# Sheet1.net
KiCad netlist of a schematic drawn in Altium Designer
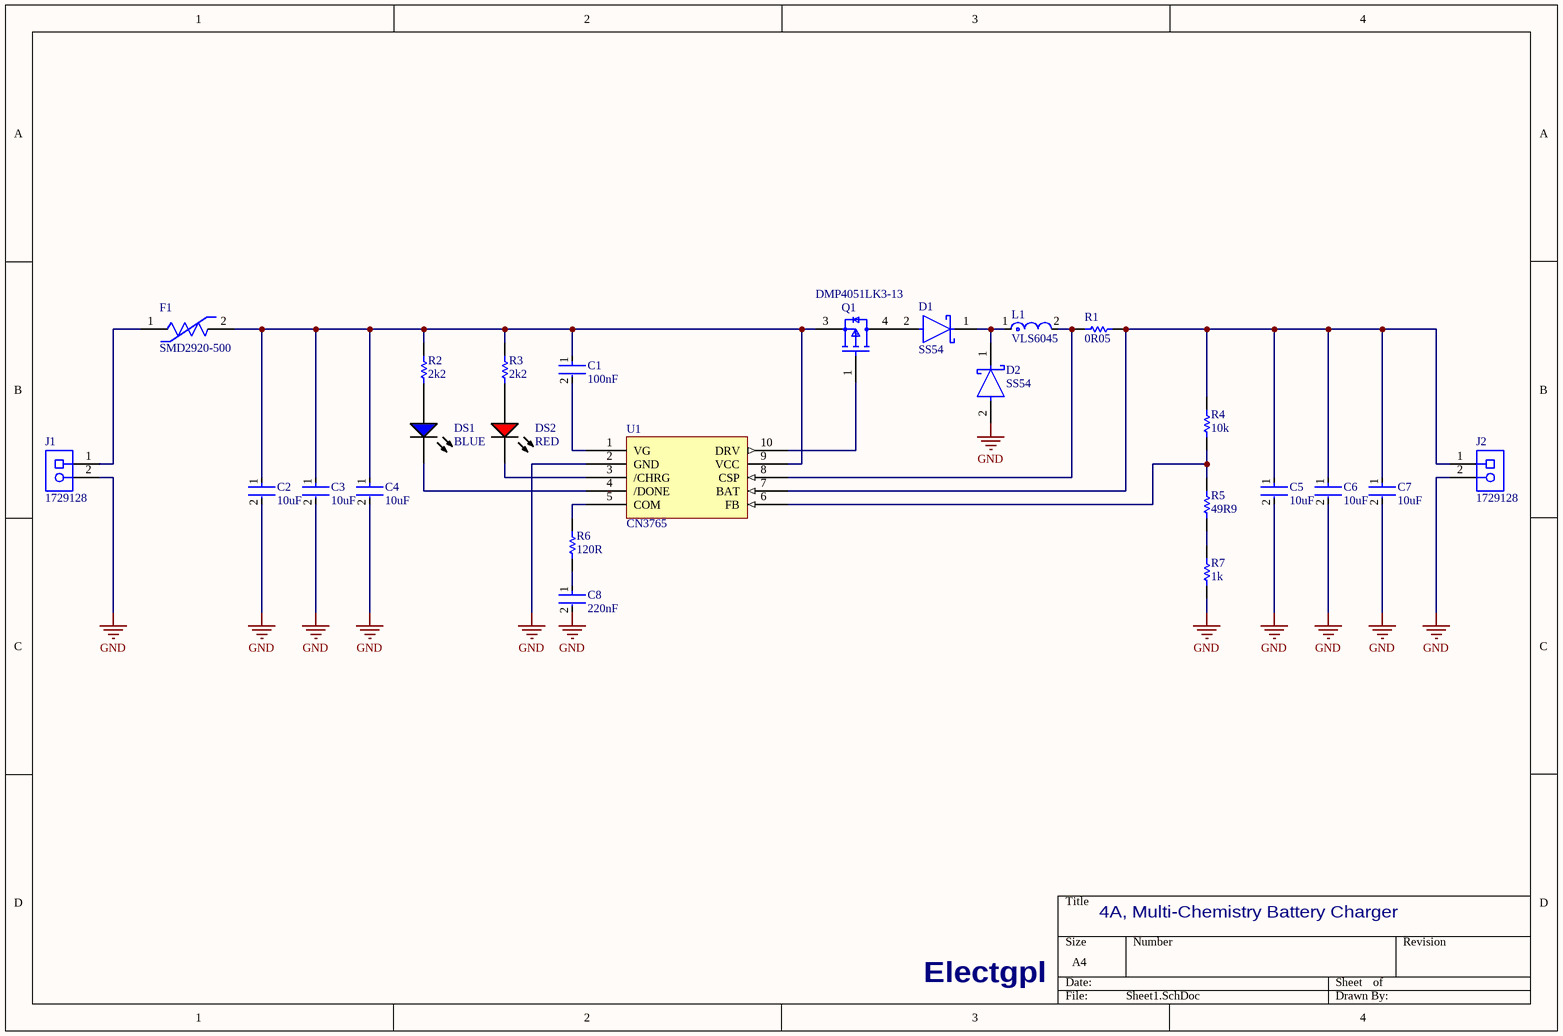
[diagram p0: Sheet1.SchDoc]

(export (version "E")
  (design (tool "Eeschema 10.0.6"))
  (components
    (comp (ref "C1")
      (value "100nF")
      (footprint "FP-C0603C-CF-MFG")
      (description "CAP CER 0.22UF 25V 10% X7R 0603")
      (fields
        (field (name "MANUFACTURER") "KEMET")
        (field (name "MANUFACTURER PART NUMBER") "C0603C224K3RACTU")
      )
      (libsource (lib "Altium Content Vault") (part "b4654b650e69147ec39a6b967a45e02"))
    )
    (comp (ref "C2")
      (value "10uF")
      (footprint "FP-GRM21B-0_1-IPC_C")
      (description "Chip Multilayer Ceramic Capacitors for General Purpose, 0805, 10uF, X5R, 15%, 10%, 16V")
      (fields (field (name "TOLERANCE") "10%") (field (name "VOLTAGE") "16V"))
      (libsource (lib "Altium Content Vault") (part "b4654b650e69147ec39a6b967a45e02"))
    )
    (comp (ref "C3")
      (value "10uF")
      (footprint "FP-GRM21B-0_1-IPC_C")
      (description "Chip Multilayer Ceramic Capacitors for General Purpose, 0805, 10uF, X5R, 15%, 10%, 16V")
      (fields (field (name "TOLERANCE") "10%") (field (name "VOLTAGE") "16V"))
      (libsource (lib "Altium Content Vault") (part "b4654b650e69147ec39a6b967a45e02"))
    )
    (comp (ref "C4")
      (value "10uF")
      (footprint "FP-GRM21B-0_1-IPC_C")
      (description "Chip Multilayer Ceramic Capacitors for General Purpose, 0805, 10uF, X5R, 15%, 10%, 16V")
      (fields (field (name "TOLERANCE") "10%") (field (name "VOLTAGE") "16V"))
      (libsource (lib "Altium Content Vault") (part "b4654b650e69147ec39a6b967a45e02"))
    )
    (comp (ref "C5")
      (value "10uF")
      (footprint "FP-GRM21B-0_1-IPC_C")
      (description "Chip Multilayer Ceramic Capacitors for General Purpose, 0805, 10uF, X5R, 15%, 10%, 16V")
      (fields (field (name "TOLERANCE") "10%") (field (name "VOLTAGE") "16V"))
      (libsource (lib "Altium Content Vault") (part "b4654b650e69147ec39a6b967a45e02"))
    )
    (comp (ref "C6")
      (value "10uF")
      (footprint "FP-GRM21B-0_1-IPC_C")
      (description "Chip Multilayer Ceramic Capacitors for General Purpose, 0805, 10uF, X5R, 15%, 10%, 16V")
      (fields (field (name "TOLERANCE") "10%") (field (name "VOLTAGE") "16V"))
      (libsource (lib "Altium Content Vault") (part "b4654b650e69147ec39a6b967a45e02"))
    )
    (comp (ref "C7")
      (value "10uF")
      (footprint "FP-GRM21B-0_1-IPC_C")
      (description "Chip Multilayer Ceramic Capacitors for General Purpose, 0805, 10uF, X5R, 15%, 10%, 16V")
      (fields (field (name "TOLERANCE") "10%") (field (name "VOLTAGE") "16V"))
      (libsource (lib "Altium Content Vault") (part "b4654b650e69147ec39a6b967a45e02"))
    )
    (comp (ref "C8")
      (value "220nF")
      (footprint "FP-C0603C-CF-MFG")
      (description "CAP CER 0.22UF 25V 10% X7R 0603")
      (fields
        (field (name "MANUFACTURER") "KEMET")
        (field (name "MANUFACTURER PART NUMBER") "C0603C224K3RACTU")
      )
      (libsource (lib "Altium Content Vault") (part "b4654b650e69147ec39a6b967a45e02"))
    )
    (comp (ref "D1")
      (value "SS54")
      (footprint "FP-SMB-MFG")
      (description "DIODE SCHOTTKY 150V 3A SMB")
      (fields
        (field (name "MANUFACTURER PART NUMBER") "STPS3150U")
        (field (name "OCTOPART") "https://octopart.com/stps3150u-stmicroelectronics-39552976")
      )
      (libsource (lib "Altium Content Vault") (part "fefb30dabb5d097ae2f038500735429"))
    )
    (comp (ref "D2")
      (value "SS54")
      (footprint "FP-SMB-MFG")
      (description "DIODE SCHOTTKY 150V 3A SMB")
      (fields
        (field (name "MANUFACTURER PART NUMBER") "STPS3150U")
        (field (name "OCTOPART") "https://octopart.com/stps3150u-stmicroelectronics-39552976")
      )
      (libsource (lib "Altium Content Vault") (part "fefb30dabb5d097ae2f038500735429"))
    )
    (comp (ref "DS1")
      (value "BLUE")
      (footprint "VISH-TLMX1100-2_V")
      (description "Blue LED, 10 mA, 3.9 V, -40 to 100 degC, 2-Pin SMD (0603), RoHS, Tape and Reel")
      (fields (field (name "TOLERANCE") "10%"))
      (libsource (lib "Altium Content Vault") (part "LED-BLUE-AK-2"))
    )
    (comp (ref "DS2")
      (value "RED")
      (footprint "VISH-TLMS1000_V")
      (description "Low Current LED, 40 mW, 1.8 V, -40 to 100 degC, 2-Pin SMD (0603), RoHS, Tape and Reel")
      (fields (field (name "MANUFACTURER") "Vishay"))
      (libsource (lib "Altium Content Vault") (part "LED-RED-AK-2"))
    )
    (comp (ref "F1")
      (value "SMD2920-500")
      (footprint "FP-2920L-MFG")
      (description "PTC RESET FUSE 60V 1.1A 2920")
      (fields
        (field (name "MANUFACTURER PART NUMBER") "2920L110/60MR")
        (field (name "MANUFACTURER") "Littelfuse")
      )
      (libsource (lib "Altium Content Vault") (part "fc31388045fc42ab786d6d00b506e9f"))
    )
    (comp (ref "J1")
      (value "1729128")
      (footprint "PHOE-1729128-2_V")
      (description "PCB Terminal Block, 13.5 A, 400 V, 2-Pin THD, RoHS, Bulk")
      (fields (field (name "MANUFACTURER") "Phoenix Contact"))
      (libsource (lib "Altium Content Vault") (part "CN-2P-F-R2"))
    )
    (comp (ref "J2")
      (value "1729128")
      (footprint "PHOE-1729128-2_V")
      (description "PCB Terminal Block, 13.5 A, 400 V, 2-Pin THD, RoHS, Bulk")
      (fields (field (name "MANUFACTURER") "Phoenix Contact"))
      (libsource (lib "") (part "CN-2P-F-R2_1"))
    )
    (comp (ref "L1")
      (value "VLS6045")
      (footprint "FP-VLS6045EX-100M-MFG")
      (description "FIXED IND 10UH 3.4A 61 MOHM SMD")
      (fields (field (name "TOLERANCE") "20%"))
      (libsource (lib "Altium Content Vault") (part "4cc4b267dca4c8e51f7102f422741d8"))
    )
    (comp (ref "Q1")
      (value "DMP4051LK3-13")
      (footprint "FP-TO252-MFG")
      (description "MOSFET P-CH 40V 7.2A DPAK")
      (fields
        (field (name "OCTOPART") "https://octopart.com/dmp4051lk3-13-diodes+inc.-17931392")
        (field (name "MANUFACTURER") "Diodes Inc.")
      )
      (libsource (lib "Altium Content Vault") (part "1e44a2d80e7b38498a768d39b468498"))
    )
    (comp (ref "R1")
      (value "0R05")
      (footprint "RESC3216X89X51LL25T25")
      (fields (field (name "MANUFACTURER") "Vishay Dale") (field (name "PART NUMBER") "WSL1206R0500FEA"))
      (libsource (lib "Altium Content Vault") (part "RES"))
    )
    (comp (ref "R2")
      (value "2k2")
      (footprint "RESC1609X55X30LL15T15")
      (description "Chip Resistor, 10 KOhm, +/- 1%, 0.1 W, -55 to 155 degC, 0603 (1608 Metric), RoHS, Tape and Reel")
      (fields (field (name "TOLERANCE") "1%") (field (name "MANUFACTURER") "Panasonic"))
      (libsource (lib "Altium Content Vault") (part "RES-2"))
    )
    (comp (ref "R3")
      (value "2k2")
      (footprint "RESC1609X55X30LL15T15")
      (description "Chip Resistor, 10 KOhm, +/- 1%, 0.1 W, -55 to 155 degC, 0603 (1608 Metric), RoHS, Tape and Reel")
      (fields (field (name "TOLERANCE") "1%") (field (name "MANUFACTURER") "Panasonic"))
      (libsource (lib "Altium Content Vault") (part "RES-2"))
    )
    (comp (ref "R4")
      (value "10k")
      (footprint "RESC1609X55X30LL15T15")
      (description "Chip Resistor, 10 KOhm, +/- 1%, 0.1 W, -55 to 155 degC, 0603 (1608 Metric), RoHS, Tape and Reel")
      (fields (field (name "TOLERANCE") "1%") (field (name "MANUFACTURER") "Panasonic"))
      (libsource (lib "Altium Content Vault") (part "RES-2"))
    )
    (comp (ref "R5")
      (value "49R9")
      (footprint "RESC1609X55X30LL15T15")
      (description "Chip Resistor, 10 KOhm, +/- 1%, 0.1 W, -55 to 155 degC, 0603 (1608 Metric), RoHS, Tape and Reel")
      (fields (field (name "TOLERANCE") "1%") (field (name "MANUFACTURER") "Panasonic"))
      (libsource (lib "Altium Content Vault") (part "RES-2"))
    )
    (comp (ref "R6")
      (value "120R")
      (footprint "RESC1609X55X30LL15T15")
      (description "Chip Resistor, 10 KOhm, +/- 1%, 0.1 W, -55 to 155 degC, 0603 (1608 Metric), RoHS, Tape and Reel")
      (fields (field (name "TOLERANCE") "1%") (field (name "MANUFACTURER") "Panasonic"))
      (libsource (lib "Altium Content Vault") (part "RES-2"))
    )
    (comp (ref "R7")
      (value "1k")
      (footprint "RESC1609X55X30LL15T15")
      (description "Chip Resistor, 10 KOhm, +/- 1%, 0.1 W, -55 to 155 degC, 0603 (1608 Metric), RoHS, Tape and Reel")
      (fields (field (name "TOLERANCE") "1%") (field (name "MANUFACTURER") "Panasonic"))
      (libsource (lib "Altium Content Vault") (part "RES-2"))
    )
    (comp (ref "U1")
      (value "CN3765")
      (footprint "SOP100P600X175-10N")
      (description "SSOP-10 Battery Management ICs ROHS")
      (libsource (lib "Electgpl (YouTube)") (part "CN3765-Symbol-1"))
    )
  )
  (nets
    (net (code "1") (name "GND") (class "Default")
      (node (ref "C2") (pin "2") (pinfunction "2_2") (pintype "passive"))
      (node (ref "C3") (pin "2") (pinfunction "2_2") (pintype "passive"))
      (node (ref "C4") (pin "2") (pinfunction "2_2") (pintype "passive"))
      (node (ref "C5") (pin "2") (pinfunction "2_2") (pintype "passive"))
      (node (ref "C6") (pin "2") (pinfunction "2_2") (pintype "passive"))
      (node (ref "C7") (pin "2") (pinfunction "2_2") (pintype "passive"))
      (node (ref "C8") (pin "2") (pinfunction "2_2") (pintype "passive"))
      (node (ref "D2") (pin "2") (pinfunction "A_2") (pintype "passive"))
      (node (ref "J1") (pin "2") (pinfunction "2_2") (pintype "passive"))
      (node (ref "J2") (pin "2") (pinfunction "2_2") (pintype "passive"))
      (node (ref "R7") (pin "1") (pinfunction "1_1") (pintype "passive"))
      (node (ref "U1") (pin "2") (pinfunction "GND_2") (pintype "power_in"))
    )
    (net (code "2") (name "Net-(C8-Pad1)") (class "Default")
      (node (ref "C8") (pin "1") (pinfunction "1_1") (pintype "passive"))
      (node (ref "R6") (pin "1") (pinfunction "1_1") (pintype "passive"))
    )
    (net (code "3") (name "Net-(D1-A)") (class "Default")
      (node (ref "D1") (pin "2") (pinfunction "A_2") (pintype "passive"))
      (node (ref "Q1") (pin "4") (pinfunction "D_4") (pintype "passive"))
    )
    (net (code "4") (name "Net-(D1-K)") (class "Default")
      (node (ref "D1") (pin "1") (pinfunction "K_1") (pintype "passive"))
      (node (ref "D2") (pin "1") (pinfunction "K_1") (pintype "passive"))
      (node (ref "L1") (pin "1") (pinfunction "1_1") (pintype "passive"))
    )
    (net (code "5") (name "Net-(DS1-A)") (class "Default")
      (node (ref "DS1") (pin "1") (pinfunction "A_1") (pintype "passive"))
      (node (ref "R2") (pin "1") (pinfunction "1_1") (pintype "passive"))
    )
    (net (code "6") (name "Net-(DS1-K)") (class "Default")
      (node (ref "DS1") (pin "2") (pinfunction "K_2") (pintype "passive"))
      (node (ref "U1") (pin "4") (pinfunction "/DONE_4") (pintype "open_collector"))
    )
    (net (code "7") (name "Net-(DS2-A)") (class "Default")
      (node (ref "DS2") (pin "1") (pinfunction "A_1") (pintype "passive"))
      (node (ref "R3") (pin "1") (pinfunction "1_1") (pintype "passive"))
    )
    (net (code "8") (name "Net-(DS2-K)") (class "Default")
      (node (ref "DS2") (pin "2") (pinfunction "K_2") (pintype "passive"))
      (node (ref "U1") (pin "3") (pinfunction "/CHRG_3") (pintype "open_collector"))
    )
    (net (code "9") (name "Net-(F1-Pad1)") (class "Default")
      (node (ref "F1") (pin "1") (pinfunction "1_1") (pintype "passive"))
      (node (ref "J1") (pin "1") (pinfunction "1_1") (pintype "passive"))
    )
    (net (code "10") (name "Net-(Q1-G)") (class "Default")
      (node (ref "Q1") (pin "1") (pinfunction "G_1") (pintype "passive"))
      (node (ref "U1") (pin "10") (pinfunction "DRV_10") (pintype "output"))
    )
    (net (code "11") (name "Net-(Q1-S)") (class "Default")
      (node (ref "C1") (pin "1") (pinfunction "1_1") (pintype "passive"))
      (node (ref "C2") (pin "1") (pinfunction "1_1") (pintype "passive"))
      (node (ref "C3") (pin "1") (pinfunction "1_1") (pintype "passive"))
      (node (ref "C4") (pin "1") (pinfunction "1_1") (pintype "passive"))
      (node (ref "F1") (pin "2") (pinfunction "2_2") (pintype "passive"))
      (node (ref "Q1") (pin "3") (pinfunction "S_3") (pintype "passive"))
      (node (ref "R2") (pin "2") (pinfunction "2_2") (pintype "passive"))
      (node (ref "R3") (pin "2") (pinfunction "2_2") (pintype "passive"))
      (node (ref "U1") (pin "9") (pinfunction "VCC_9") (pintype "power_in"))
    )
    (net (code "12") (name "Net-(R5-Pad1)") (class "Default")
      (node (ref "R5") (pin "1") (pinfunction "1_1") (pintype "passive"))
      (node (ref "R7") (pin "2") (pinfunction "2_2") (pintype "passive"))
    )
    (net (code "13") (name "Net-(U1-BAT)") (class "Default")
      (node (ref "C5") (pin "1") (pinfunction "1_1") (pintype "passive"))
      (node (ref "C6") (pin "1") (pinfunction "1_1") (pintype "passive"))
      (node (ref "C7") (pin "1") (pinfunction "1_1") (pintype "passive"))
      (node (ref "J2") (pin "1") (pinfunction "1_1") (pintype "passive"))
      (node (ref "R1") (pin "2") (pinfunction "2_2") (pintype "passive"))
      (node (ref "R4") (pin "2") (pinfunction "2_2") (pintype "passive"))
      (node (ref "U1") (pin "7") (pinfunction "BAT_7") (pintype "input"))
    )
    (net (code "14") (name "Net-(U1-COM)") (class "Default")
      (node (ref "R6") (pin "2") (pinfunction "2_2") (pintype "passive"))
      (node (ref "U1") (pin "5") (pinfunction "COM_5") (pintype "passive"))
    )
    (net (code "15") (name "Net-(U1-CSP)") (class "Default")
      (node (ref "L1") (pin "2") (pinfunction "2_2") (pintype "passive"))
      (node (ref "R1") (pin "1") (pinfunction "1_1") (pintype "passive"))
      (node (ref "U1") (pin "8") (pinfunction "CSP_8") (pintype "input"))
    )
    (net (code "16") (name "Net-(U1-FB)") (class "Default")
      (node (ref "R4") (pin "1") (pinfunction "1_1") (pintype "passive"))
      (node (ref "R5") (pin "2") (pinfunction "2_2") (pintype "passive"))
      (node (ref "U1") (pin "6") (pinfunction "FB_6") (pintype "input"))
    )
    (net (code "17") (name "Net-(U1-VG)") (class "Default")
      (node (ref "C1") (pin "2") (pinfunction "2_2") (pintype "passive"))
      (node (ref "U1") (pin "1") (pinfunction "VG_1") (pintype "power_in"))
    )
  )
)
